# Vision.net
KiCad netlist of a schematic drawn in EAGLE
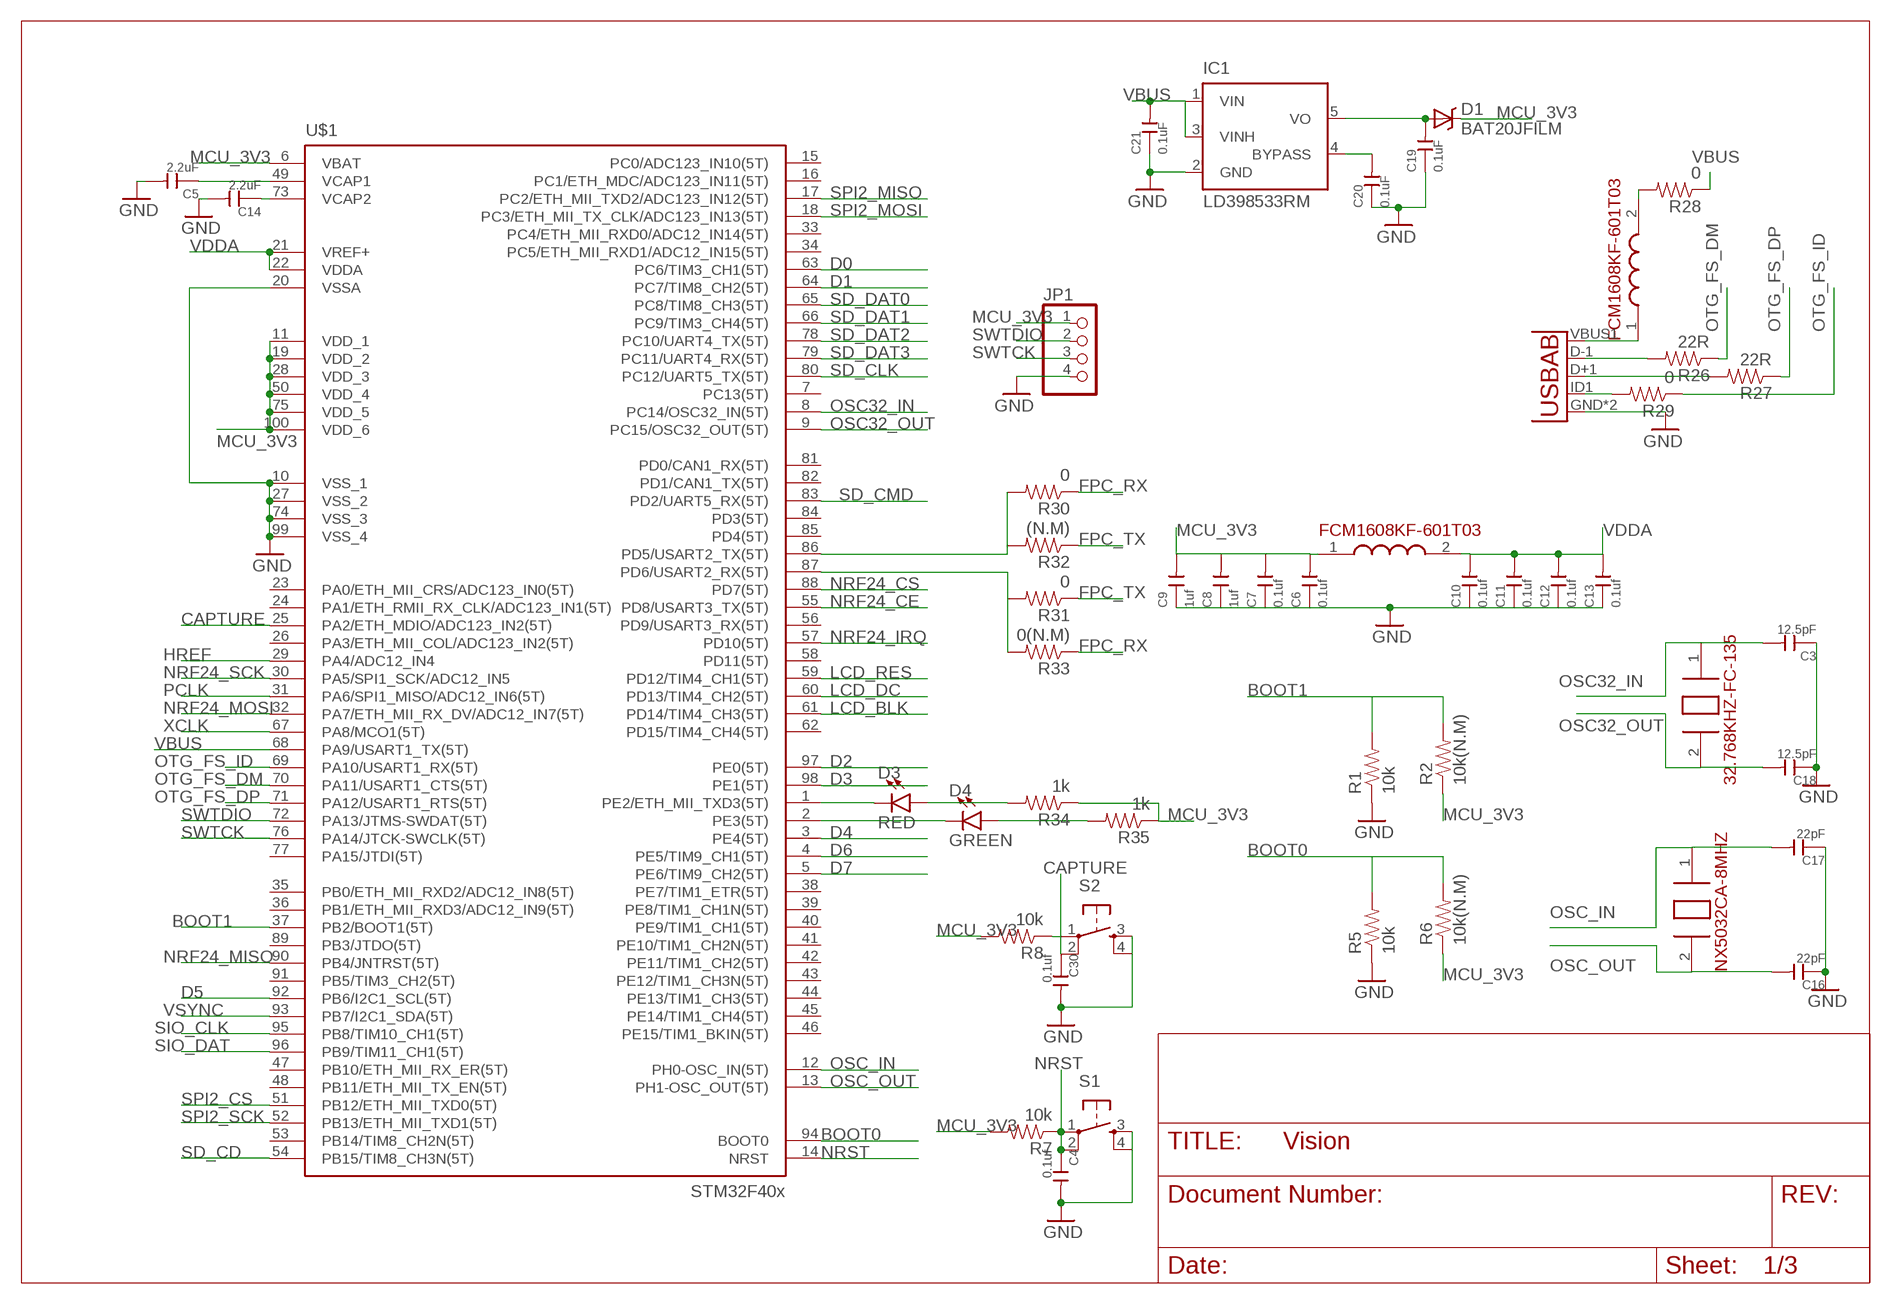
[diagram p0: schematic, sheet 1]
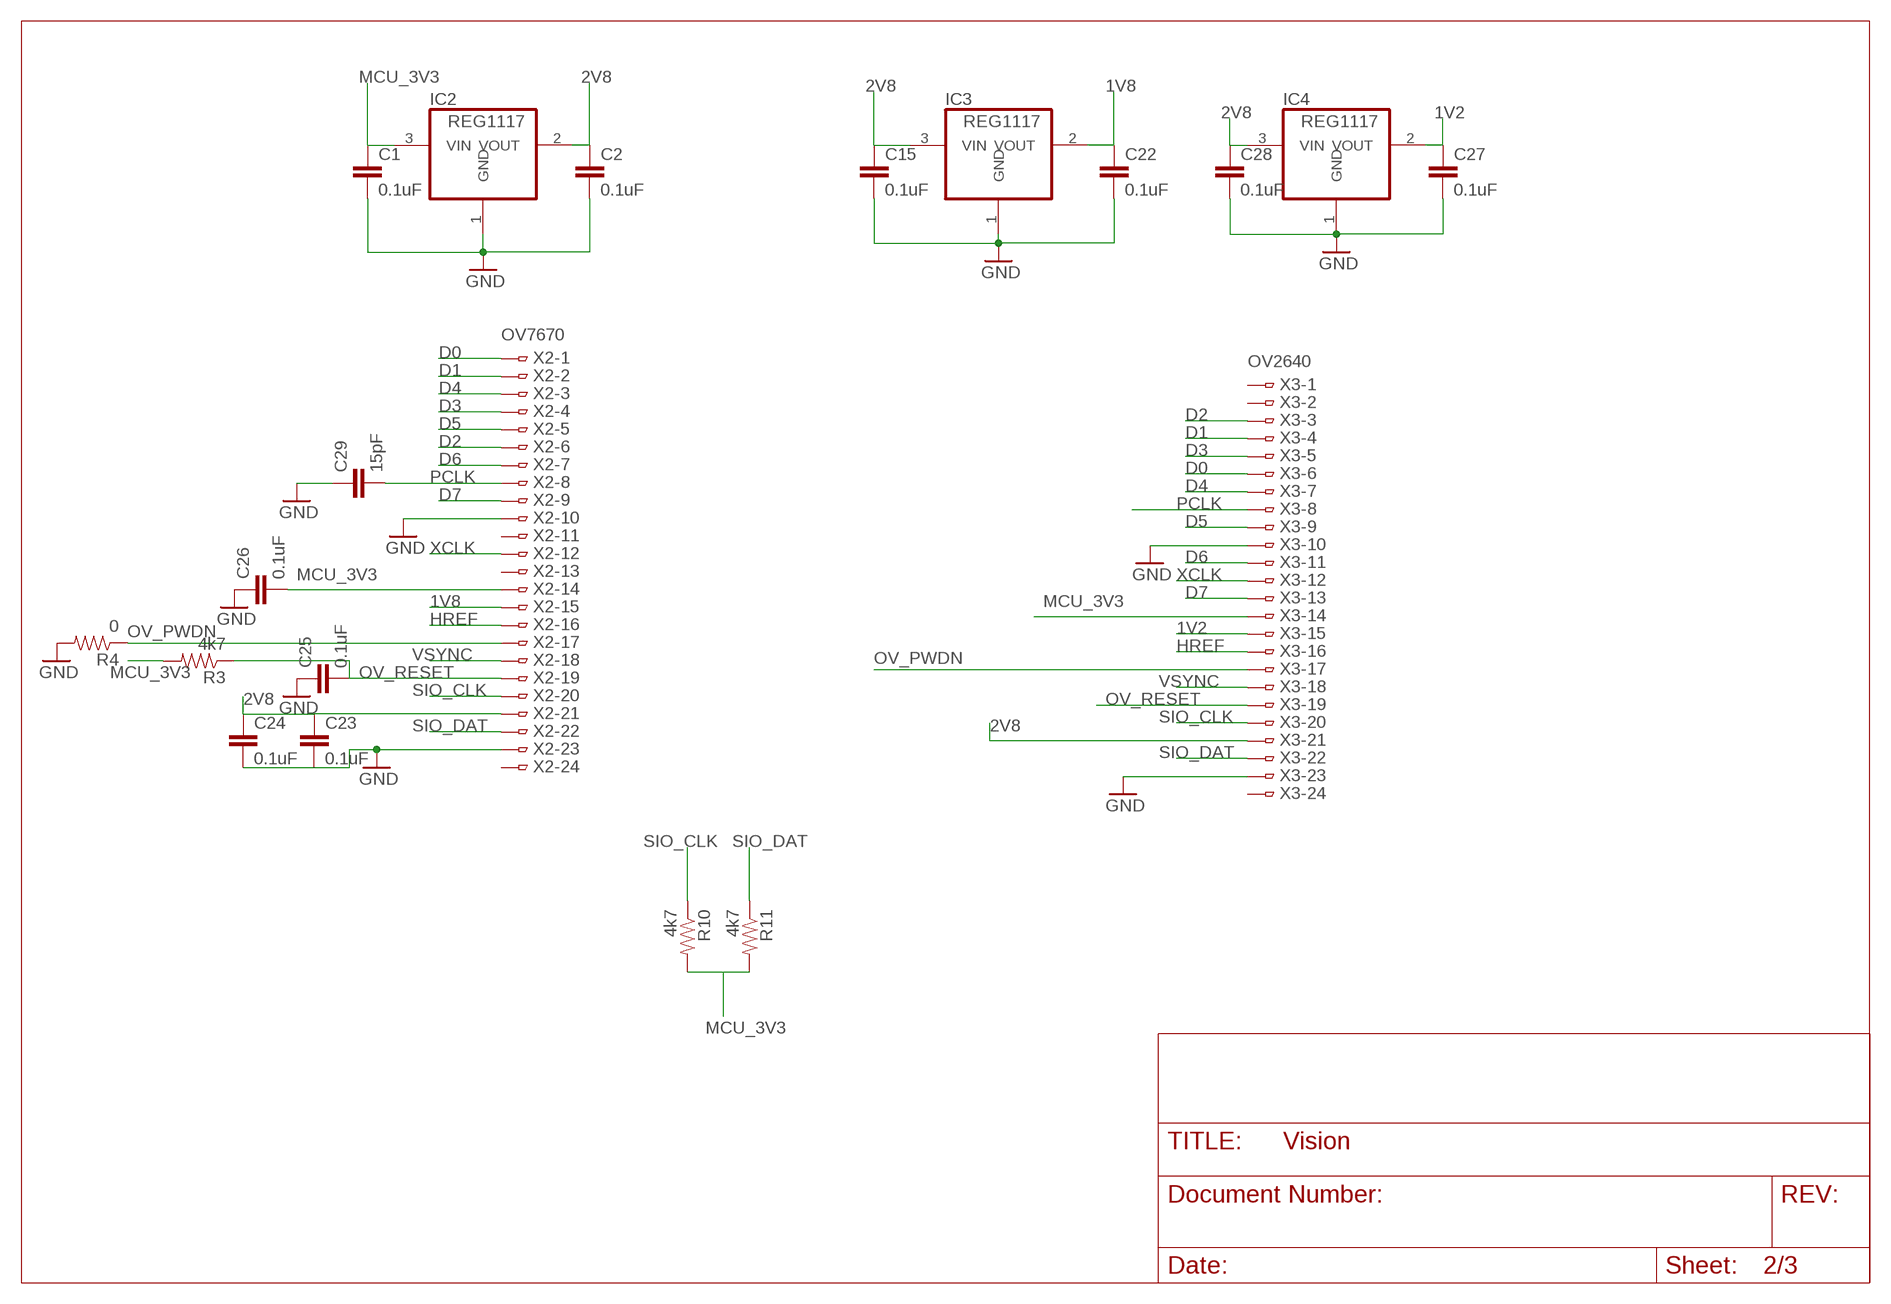
[diagram p1: schematic, sheet 2]
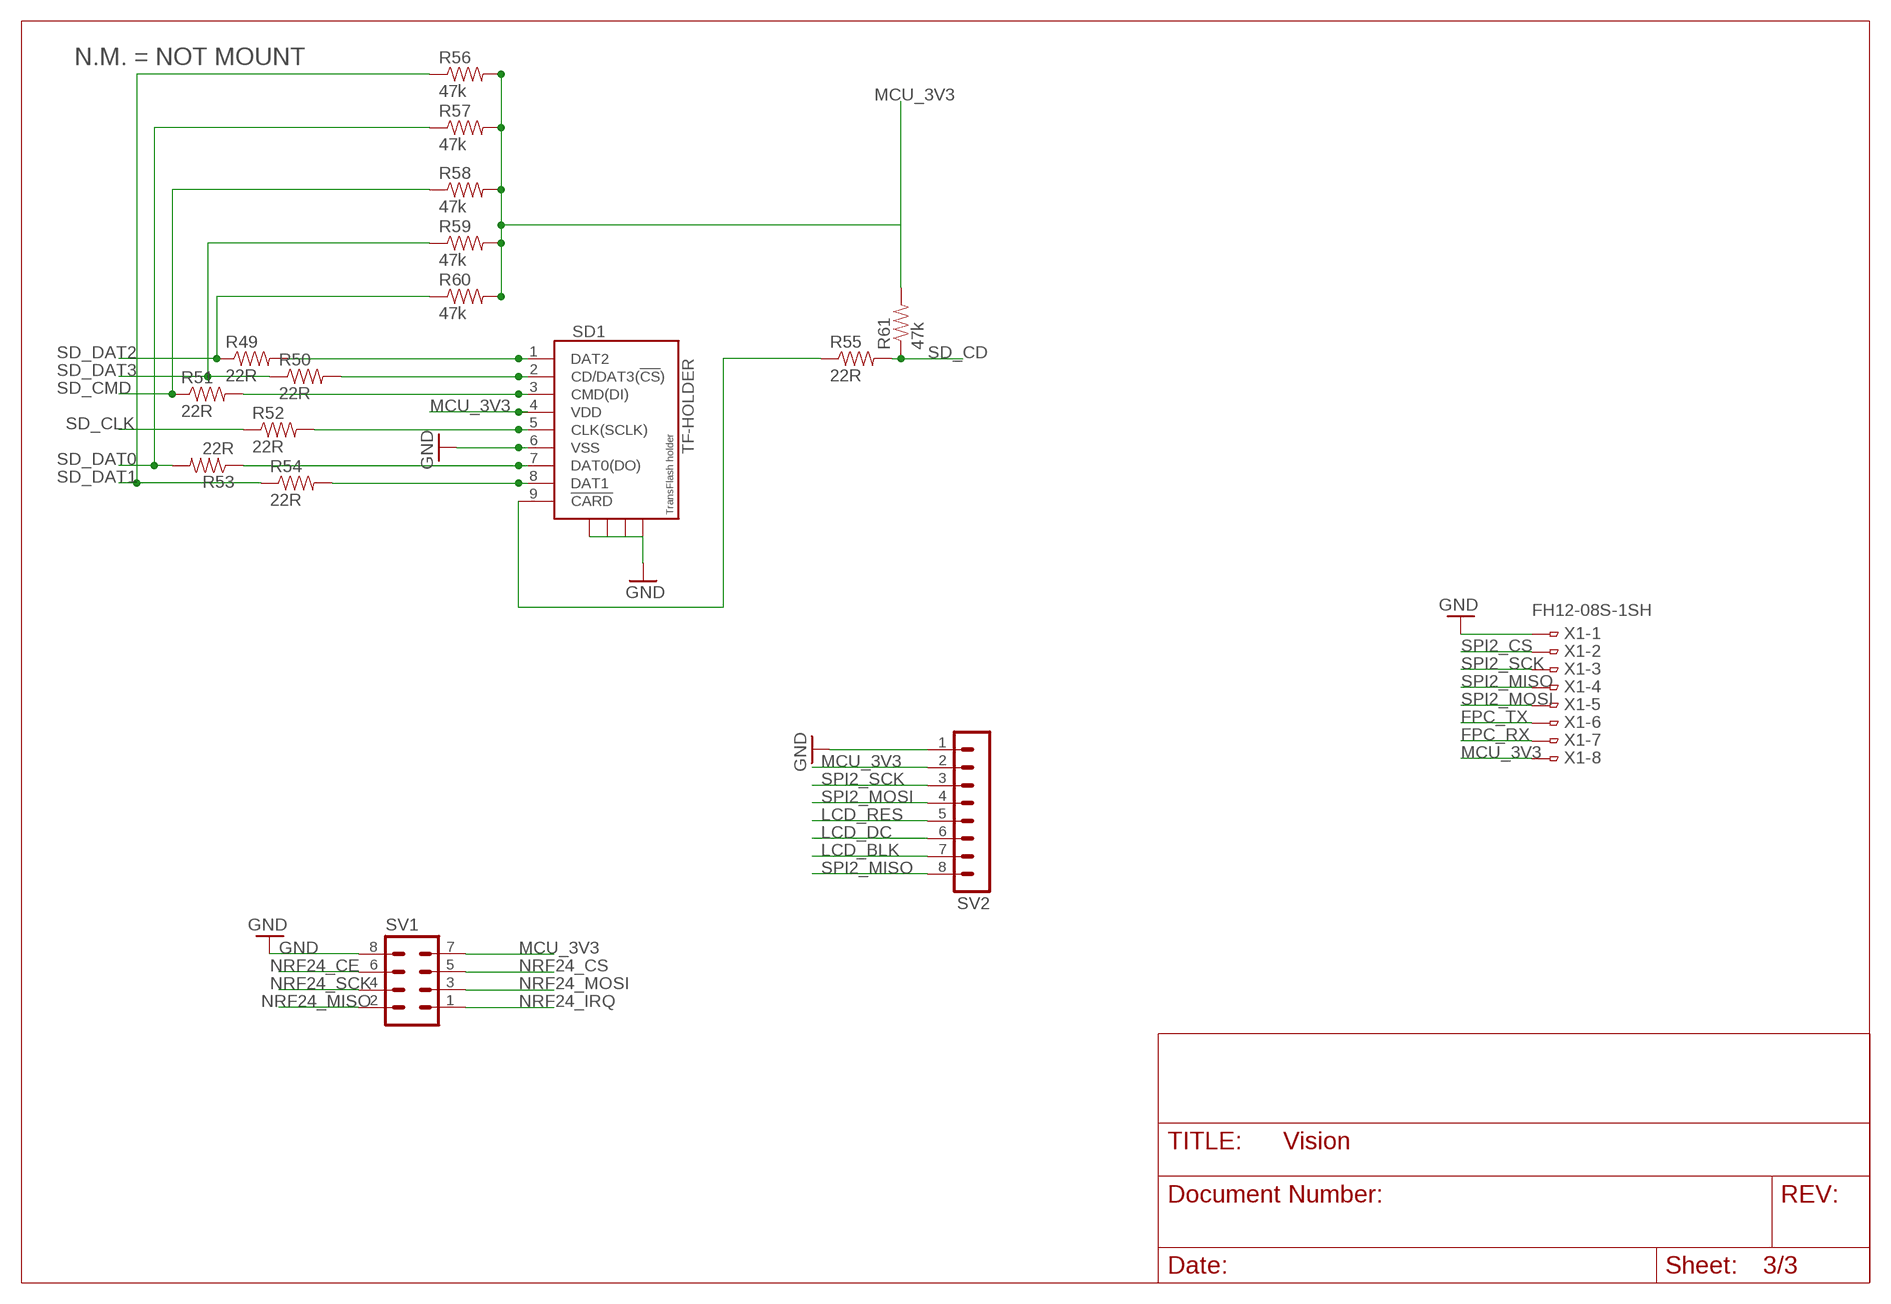
[diagram p2: schematic, sheet 3]

(export (version "E")
  (design (tool "Eeschema 10.0.6"))
  (components
    (comp (ref "C1")
      (value "0.1uF")
      (footprint "eagle-import:0805")
      (libsource (lib "eagle-import") (part "1.0UF-25V-+80/-20(0805)"))
    )
    (comp (ref "C2")
      (value "0.1uF")
      (footprint "eagle-import:0805")
      (libsource (lib "eagle-import") (part "1.0UF-25V-+80/-20(0805)"))
    )
    (comp (ref "C15")
      (value "0.1uF")
      (footprint "eagle-import:0805")
      (libsource (lib "eagle-import") (part "1.0UF-25V-+80/-20(0805)"))
    )
    (comp (ref "C22")
      (value "0.1uF")
      (footprint "eagle-import:0805")
      (libsource (lib "eagle-import") (part "1.0UF-25V-+80/-20(0805)"))
    )
    (comp (ref "C23")
      (value "0.1uF")
      (footprint "eagle-import:0805")
      (libsource (lib "eagle-import") (part "1.0UF-25V-+80/-20(0805)"))
    )
    (comp (ref "C24")
      (value "0.1uF")
      (footprint "eagle-import:0805")
      (libsource (lib "eagle-import") (part "1.0UF-25V-+80/-20(0805)"))
    )
    (comp (ref "C25")
      (value "0.1uF")
      (footprint "eagle-import:0805")
      (libsource (lib "eagle-import") (part "1.0UF-25V-+80/-20(0805)"))
    )
    (comp (ref "C26")
      (value "0.1uF")
      (footprint "eagle-import:0805")
      (libsource (lib "eagle-import") (part "1.0UF-25V-+80/-20(0805)"))
    )
    (comp (ref "C27")
      (value "0.1uF")
      (footprint "eagle-import:0805")
      (libsource (lib "eagle-import") (part "1.0UF-25V-+80/-20(0805)"))
    )
    (comp (ref "C28")
      (value "0.1uF")
      (footprint "eagle-import:0805")
      (libsource (lib "eagle-import") (part "1.0UF-25V-+80/-20(0805)"))
    )
    (comp (ref "C29")
      (value "15pF")
      (footprint "eagle-import:0805")
      (libsource (lib "eagle-import") (part "1.0UF-25V-+80/-20(0805)"))
    )
    (comp (ref "IC2")
      (value "REG1117")
      (footprint "eagle-import:SOT223")
      (libsource (lib "eagle-import") (part "REG1117"))
    )
    (comp (ref "IC3")
      (value "REG1117")
      (footprint "eagle-import:SOT223")
      (libsource (lib "eagle-import") (part "REG1117"))
    )
    (comp (ref "IC4")
      (value "REG1117")
      (footprint "eagle-import:SOT223")
      (libsource (lib "eagle-import") (part "REG1117"))
    )
    (comp (ref "R3")
      (value "4k7")
      (footprint "eagle-import:0603")
      (libsource (lib "eagle-import") (part "0OHM1/10W5%(0603)"))
    )
    (comp (ref "R4")
      (value "0")
      (footprint "eagle-import:0603")
      (libsource (lib "eagle-import") (part "0OHM1/10W5%(0603)"))
    )
    (comp (ref "R10")
      (value "4k7")
      (footprint "eagle-import:0603")
      (libsource (lib "eagle-import") (part "0OHM1/10W5%(0603)"))
    )
    (comp (ref "R11")
      (value "4k7")
      (footprint "eagle-import:0603")
      (libsource (lib "eagle-import") (part "0OHM1/10W5%(0603)"))
    )
    (comp (ref "X2")
      (value "OV7670")
      (footprint "eagle-import:FH12-24S-0.5SH")
      (fields (field (name "MPN") "FH12-24S-0.5SH(55)"))
      (libsource (lib "eagle-import") (part "FH12-24S-0.5SH"))
    )
    (comp (ref "X3")
      (value "OV2640")
      (footprint "eagle-import:FH12-24S-0.5SH")
      (fields (field (name "MPN") "FH12-24S-0.5SH(55)"))
      (libsource (lib "eagle-import") (part "FH12-24S-0.5SH"))
    )
    (comp (ref "R49")
      (value "22R")
      (footprint "eagle-import:0603-RES")
      (libsource (lib "eagle-import") (part "100OHM1/10W1%(0603)"))
    )
    (comp (ref "R50")
      (value "22R")
      (footprint "eagle-import:0603-RES")
      (libsource (lib "eagle-import") (part "100OHM1/10W1%(0603)"))
    )
    (comp (ref "R51")
      (value "22R")
      (footprint "eagle-import:0603-RES")
      (libsource (lib "eagle-import") (part "100OHM1/10W1%(0603)"))
    )
    (comp (ref "R52")
      (value "22R")
      (footprint "eagle-import:0603-RES")
      (libsource (lib "eagle-import") (part "100OHM1/10W1%(0603)"))
    )
    (comp (ref "R53")
      (value "22R")
      (footprint "eagle-import:0603-RES")
      (libsource (lib "eagle-import") (part "100OHM1/10W1%(0603)"))
    )
    (comp (ref "R54")
      (value "22R")
      (footprint "eagle-import:0603-RES")
      (libsource (lib "eagle-import") (part "100OHM1/10W1%(0603)"))
    )
    (comp (ref "R55")
      (value "22R")
      (footprint "eagle-import:0603-RES")
      (libsource (lib "eagle-import") (part "100OHM1/10W1%(0603)"))
    )
    (comp (ref "R56")
      (value "47k")
      (footprint "eagle-import:0603-RES")
      (libsource (lib "eagle-import") (part "100OHM1/10W1%(0603)"))
    )
    (comp (ref "R57")
      (value "47k")
      (footprint "eagle-import:0603-RES")
      (libsource (lib "eagle-import") (part "100OHM1/10W1%(0603)"))
    )
    (comp (ref "R58")
      (value "47k")
      (footprint "eagle-import:0603-RES")
      (libsource (lib "eagle-import") (part "100OHM1/10W1%(0603)"))
    )
    (comp (ref "R59")
      (value "47k")
      (footprint "eagle-import:0603-RES")
      (libsource (lib "eagle-import") (part "100OHM1/10W1%(0603)"))
    )
    (comp (ref "R60")
      (value "47k")
      (footprint "eagle-import:0603-RES")
      (libsource (lib "eagle-import") (part "100OHM1/10W1%(0603)"))
    )
    (comp (ref "R61")
      (value "47k")
      (footprint "eagle-import:0603-RES")
      (libsource (lib "eagle-import") (part "100OHM1/10W1%(0603)"))
    )
    (comp (ref "SD1")
      (value "TF-HOLDER")
      (footprint "eagle-import:TF-PULL")
      (libsource (lib "eagle-import") (part "TF-HOLDER"))
    )
    (comp (ref "SV1")
      (value "MA04-2")
      (footprint "eagle-import:MA04-2")
      (libsource (lib "eagle-import") (part "MA04-2"))
    )
    (comp (ref "SV2")
      (value "MA08-1")
      (footprint "eagle-import:MA08-1")
      (libsource (lib "eagle-import") (part "MA08-1"))
    )
    (comp (ref "X1")
      (value "FH12-08S-1SH")
      (footprint "eagle-import:FH12-08S-1SH")
      (libsource (lib "eagle-import") (part "FH12-08S-1SH"))
    )
    (comp (ref "C3")
      (value "12.5pF")
      (footprint "eagle-import:C0603")
      (fields (field (name "MPN") "CC0603KRX5R6BB475"))
      (libsource (lib "eagle-import") (part "CERAMIC-4.7UF-10V-10%-X5R(0603)"))
    )
    (comp (ref "C4")
      (value "0.1uf")
      (footprint "eagle-import:C0603")
      (fields (field (name "MPN") "CC0603KRX5R6BB475"))
      (libsource (lib "eagle-import") (part "CERAMIC-4.7UF-10V-10%-X5R(0603)"))
    )
    (comp (ref "C5")
      (value "2.2uF")
      (footprint "eagle-import:C0603")
      (libsource (lib "eagle-import") (part "CERAMIC-0.5PF-50V-0.1PF-NPO(0603)"))
    )
    (comp (ref "C6")
      (value "0.1uf")
      (footprint "eagle-import:C0603")
      (fields (field (name "MPN") "CC0603KRX5R6BB475"))
      (libsource (lib "eagle-import") (part "CERAMIC-4.7UF-10V-10%-X5R(0603)"))
    )
    (comp (ref "C7")
      (value "0.1uf")
      (footprint "eagle-import:C0603")
      (fields (field (name "MPN") "CC0603KRX5R6BB475"))
      (libsource (lib "eagle-import") (part "CERAMIC-4.7UF-10V-10%-X5R(0603)"))
    )
    (comp (ref "C8")
      (value "1uf")
      (footprint "eagle-import:C0603")
      (fields (field (name "MPN") "CC0603KRX5R6BB475"))
      (libsource (lib "eagle-import") (part "CERAMIC-4.7UF-10V-10%-X5R(0603)"))
    )
    (comp (ref "C9")
      (value "1uf")
      (footprint "eagle-import:C0603")
      (fields (field (name "MPN") "CC0603KRX5R6BB475"))
      (libsource (lib "eagle-import") (part "CERAMIC-4.7UF-10V-10%-X5R(0603)"))
    )
    (comp (ref "C10")
      (value "0.1uf")
      (footprint "eagle-import:C0603")
      (fields (field (name "MPN") "CC0603KRX5R6BB475"))
      (libsource (lib "eagle-import") (part "CERAMIC-4.7UF-10V-10%-X5R(0603)"))
    )
    (comp (ref "C11")
      (value "0.1uf")
      (footprint "eagle-import:C0603")
      (fields (field (name "MPN") "CC0603KRX5R6BB475"))
      (libsource (lib "eagle-import") (part "CERAMIC-4.7UF-10V-10%-X5R(0603)"))
    )
    (comp (ref "C12")
      (value "0.1uf")
      (footprint "eagle-import:C0603")
      (fields (field (name "MPN") "CC0603KRX5R6BB475"))
      (libsource (lib "eagle-import") (part "CERAMIC-4.7UF-10V-10%-X5R(0603)"))
    )
    (comp (ref "C13")
      (value "0.1uf")
      (footprint "eagle-import:C0603")
      (fields (field (name "MPN") "CC0603KRX5R6BB475"))
      (libsource (lib "eagle-import") (part "CERAMIC-4.7UF-10V-10%-X5R(0603)"))
    )
    (comp (ref "C14")
      (value "2.2uF")
      (footprint "eagle-import:C0603")
      (libsource (lib "eagle-import") (part "CERAMIC-0.5PF-50V-0.1PF-NPO(0603)"))
    )
    (comp (ref "C16")
      (value "22pF")
      (footprint "eagle-import:C0603")
      (fields (field (name "MPN") "CC0603KRX5R6BB475"))
      (libsource (lib "eagle-import") (part "CERAMIC-4.7UF-10V-10%-X5R(0603)"))
    )
    (comp (ref "C17")
      (value "22pF")
      (footprint "eagle-import:C0603")
      (fields (field (name "MPN") "CC0603KRX5R6BB475"))
      (libsource (lib "eagle-import") (part "CERAMIC-4.7UF-10V-10%-X5R(0603)"))
    )
    (comp (ref "C18")
      (value "12.5pF")
      (footprint "eagle-import:C0603")
      (fields (field (name "MPN") "CC0603KRX5R6BB475"))
      (libsource (lib "eagle-import") (part "CERAMIC-4.7UF-10V-10%-X5R(0603)"))
    )
    (comp (ref "C19")
      (value "0.1uF")
      (footprint "eagle-import:C0603")
      (libsource (lib "eagle-import") (part "CERAMIC-0.5PF-50V-0.1PF-NPO(0603)"))
    )
    (comp (ref "C20")
      (value "0.1uF")
      (footprint "eagle-import:C0603")
      (libsource (lib "eagle-import") (part "CERAMIC-0.5PF-50V-0.1PF-NPO(0603)"))
    )
    (comp (ref "C21")
      (value "0.1uF")
      (footprint "eagle-import:C0603")
      (libsource (lib "eagle-import") (part "CERAMIC-0.5PF-50V-0.1PF-NPO(0603)"))
    )
    (comp (ref "C30")
      (value "0.1uf")
      (footprint "eagle-import:C0603")
      (fields (field (name "MPN") "CC0603KRX5R6BB475"))
      (libsource (lib "eagle-import") (part "CERAMIC-4.7UF-10V-10%-X5R(0603)"))
    )
    (comp (ref "D1")
      (value "BAT20JFILM")
      (footprint "eagle-import:SOD-323")
      (libsource (lib "eagle-import") (part "BAT20JFILM"))
    )
    (comp (ref "D3")
      (value "RED")
      (footprint "eagle-import:LED-0603")
      (libsource (lib "eagle-import") (part "LED-BLUE0603"))
    )
    (comp (ref "D4")
      (value "GREEN")
      (footprint "eagle-import:LED-0603")
      (libsource (lib "eagle-import") (part "LED-BLUE0603"))
    )
    (comp (ref "IC1")
      (value "LD398533RM")
      (footprint "eagle-import:SOT23-5L")
      (libsource (lib "eagle-import") (part "LD3985M33R"))
    )
    (comp (ref "JP1")
      (value "PINHD-1X4")
      (footprint "eagle-import:1X04")
      (libsource (lib "eagle-import") (part "PINHD-1X4"))
    )
    (comp (ref "R1")
      (value "10k")
      (footprint "eagle-import:0603")
      (libsource (lib "eagle-import") (part "0OHM1/10W5%(0603)"))
    )
    (comp (ref "R2")
      (value "10k(N.M)")
      (footprint "eagle-import:0603")
      (libsource (lib "eagle-import") (part "0OHM1/10W5%(0603)"))
    )
    (comp (ref "R5")
      (value "10k")
      (footprint "eagle-import:0603")
      (libsource (lib "eagle-import") (part "0OHM1/10W5%(0603)"))
    )
    (comp (ref "R6")
      (value "10k(N.M)")
      (footprint "eagle-import:0603")
      (libsource (lib "eagle-import") (part "0OHM1/10W5%(0603)"))
    )
    (comp (ref "R7")
      (value "10k")
      (footprint "eagle-import:0603")
      (libsource (lib "eagle-import") (part "0OHM1/10W5%(0603)"))
    )
    (comp (ref "R8")
      (value "10k")
      (footprint "eagle-import:0603")
      (libsource (lib "eagle-import") (part "0OHM1/10W5%(0603)"))
    )
    (comp (ref "R26")
      (value "22R")
      (footprint "eagle-import:0603-RES")
      (libsource (lib "eagle-import") (part "390OHM1/10W1%(0603)"))
    )
    (comp (ref "R27")
      (value "22R")
      (footprint "eagle-import:0603-RES")
      (libsource (lib "eagle-import") (part "390OHM1/10W1%(0603)"))
    )
    (comp (ref "R28")
      (value "0")
      (footprint "eagle-import:0603-RES")
      (libsource (lib "eagle-import") (part "390OHM1/10W1%(0603)"))
    )
    (comp (ref "R29")
      (value "0")
      (footprint "eagle-import:0603-RES")
      (libsource (lib "eagle-import") (part "390OHM1/10W1%(0603)"))
    )
    (comp (ref "R30")
      (value "0")
      (footprint "eagle-import:0603")
      (libsource (lib "eagle-import") (part "0OHM1/10W5%(0603)"))
    )
    (comp (ref "R31")
      (value "0")
      (footprint "eagle-import:0603")
      (libsource (lib "eagle-import") (part "0OHM1/10W5%(0603)"))
    )
    (comp (ref "R32")
      (value "(N.M)")
      (footprint "eagle-import:0603")
      (libsource (lib "eagle-import") (part "0OHM1/10W5%(0603)"))
    )
    (comp (ref "R33")
      (value "0(N.M)")
      (footprint "eagle-import:0603")
      (libsource (lib "eagle-import") (part "0OHM1/10W5%(0603)"))
    )
    (comp (ref "R34")
      (value "1k")
      (footprint "eagle-import:0603")
      (libsource (lib "eagle-import") (part "0OHM1/10W5%(0603)"))
    )
    (comp (ref "R35")
      (value "1k")
      (footprint "eagle-import:0603")
      (libsource (lib "eagle-import") (part "0OHM1/10W5%(0603)"))
    )
    (comp (ref "S1")
      (value "TAC_SWITCHSMD")
      (footprint "eagle-import:TACTILE_SWITCH_SMD")
      (libsource (lib "eagle-import") (part "TAC_SWITCHSMD"))
    )
    (comp (ref "S2")
      (value "TAC_SWITCHSMD")
      (footprint "eagle-import:TACTILE_SWITCH_SMD")
      (libsource (lib "eagle-import") (part "TAC_SWITCHSMD"))
    )
    (comp (ref "U$1")
      (value "STM32F407V")
      (footprint "eagle-import:TQFP100")
      (libsource (lib "eagle-import") (part "STM32F407V"))
    )
    (comp (ref "U$2")
      (value "NX5032CA-8MHZ")
      (footprint "eagle-import:NX5032CA-8MHZ")
      (libsource (lib "eagle-import") (part "NX5032CA-8MHZ"))
    )
    (comp (ref "U$3")
      (value "FCM1608KF-601T03")
      (footprint "eagle-import:FCM1608KF-601T03")
      (libsource (lib "eagle-import") (part "FCM1608KF-601T03"))
    )
    (comp (ref "U$4")
      (value "32.768KHZ-FC-135")
      (footprint "eagle-import:32.768KHZ-FC-135")
      (libsource (lib "eagle-import") (part "32.768KHZ-FC-135"))
    )
    (comp (ref "U$5")
      (value "FCM1608KF-601T03")
      (footprint "eagle-import:FCM1608KF-601T03")
      (libsource (lib "eagle-import") (part "FCM1608KF-601T03"))
    )
    (comp (ref "U4")
      (value "USB\"\"")
      (footprint "eagle-import:USB-MICRO-SMD")
      (libsource (lib "eagle-import") (part "USB{dblquote}{dblquote}"))
    )
  )
  (nets
    (net (code "1") (name "1V2") (class "Default")
      (node (ref "C27") (pin "1") (pinfunction "1_1") (pintype "passive"))
      (node (ref "IC4") (pin "2") (pinfunction "VOUT_2") (pintype "output"))
      (node (ref "X3") (pin "15") (pinfunction "1_15") (pintype "passive"))
    )
    (net (code "2") (name "1V8") (class "Default")
      (node (ref "C22") (pin "1") (pinfunction "1_1") (pintype "passive"))
      (node (ref "IC3") (pin "2") (pinfunction "VOUT_2") (pintype "output"))
      (node (ref "X2") (pin "15") (pinfunction "1_15") (pintype "passive"))
    )
    (net (code "3") (name "2V8") (class "Default")
      (node (ref "C15") (pin "1") (pinfunction "1_1") (pintype "passive"))
      (node (ref "C2") (pin "1") (pinfunction "1_1") (pintype "passive"))
      (node (ref "C23") (pin "1") (pinfunction "1_1") (pintype "passive"))
      (node (ref "C24") (pin "1") (pinfunction "1_1") (pintype "passive"))
      (node (ref "C28") (pin "1") (pinfunction "1_1") (pintype "passive"))
      (node (ref "IC2") (pin "2") (pinfunction "VOUT_2") (pintype "output"))
      (node (ref "IC3") (pin "3") (pinfunction "VIN_3") (pintype "input"))
      (node (ref "IC4") (pin "3") (pinfunction "VIN_3") (pintype "input"))
      (node (ref "X2") (pin "21") (pinfunction "1_21") (pintype "passive"))
      (node (ref "X3") (pin "21") (pinfunction "1_21") (pintype "passive"))
    )
    (net (code "4") (name "BOOT0") (class "Default")
      (node (ref "R5") (pin "2") (pinfunction "2_2") (pintype "passive"))
      (node (ref "R6") (pin "2") (pinfunction "2_2") (pintype "passive"))
      (node (ref "U$1") (pin "94") (pinfunction "BOOT0_94") (pintype "bidirectional"))
    )
    (net (code "5") (name "BOOT1") (class "Default")
      (node (ref "R1") (pin "2") (pinfunction "2_2") (pintype "passive"))
      (node (ref "R2") (pin "2") (pinfunction "2_2") (pintype "passive"))
      (node (ref "U$1") (pin "37") (pinfunction "PB2/BOOT1(5T)_37") (pintype "bidirectional"))
    )
    (net (code "6") (name "CAPTURE") (class "Default")
      (node (ref "C30") (pin "1") (pinfunction "1_1") (pintype "passive"))
      (node (ref "R8") (pin "1") (pinfunction "1_1") (pintype "passive"))
      (node (ref "S2") (pin "1") (pinfunction "1_1") (pintype "passive"))
      (node (ref "S2") (pin "2") (pinfunction "2_2") (pintype "passive"))
      (node (ref "U$1") (pin "25") (pinfunction "PA2/ETH_MDIO/ADC123_IN2(5T)_25") (pintype "bidirectional"))
    )
    (net (code "7") (name "D0") (class "Default")
      (node (ref "U$1") (pin "63") (pinfunction "PC6/TIM3_CH1(5T)_63") (pintype "bidirectional"))
      (node (ref "X2") (pin "1") (pinfunction "1_1") (pintype "passive"))
      (node (ref "X3") (pin "6") (pinfunction "1_6") (pintype "passive"))
    )
    (net (code "8") (name "D1") (class "Default")
      (node (ref "U$1") (pin "64") (pinfunction "PC7/TIM8_CH2(5T)_64") (pintype "bidirectional"))
      (node (ref "X2") (pin "2") (pinfunction "1_2") (pintype "passive"))
      (node (ref "X3") (pin "4") (pinfunction "1_4") (pintype "passive"))
    )
    (net (code "9") (name "D2") (class "Default")
      (node (ref "U$1") (pin "97") (pinfunction "PE0(5T)_97") (pintype "bidirectional"))
      (node (ref "X2") (pin "6") (pinfunction "1_6") (pintype "passive"))
      (node (ref "X3") (pin "3") (pinfunction "1_3") (pintype "passive"))
    )
    (net (code "10") (name "D3") (class "Default")
      (node (ref "U$1") (pin "98") (pinfunction "PE1(5T)_98") (pintype "bidirectional"))
      (node (ref "X2") (pin "4") (pinfunction "1_4") (pintype "passive"))
      (node (ref "X3") (pin "5") (pinfunction "1_5") (pintype "passive"))
    )
    (net (code "11") (name "D4") (class "Default")
      (node (ref "U$1") (pin "3") (pinfunction "PE4(5T)_3") (pintype "bidirectional"))
      (node (ref "X2") (pin "3") (pinfunction "1_3") (pintype "passive"))
      (node (ref "X3") (pin "7") (pinfunction "1_7") (pintype "passive"))
    )
    (net (code "12") (name "D5") (class "Default")
      (node (ref "U$1") (pin "92") (pinfunction "PB6/I2C1_SCL(5T)_92") (pintype "bidirectional"))
      (node (ref "X2") (pin "5") (pinfunction "1_5") (pintype "passive"))
      (node (ref "X3") (pin "9") (pinfunction "1_9") (pintype "passive"))
    )
    (net (code "13") (name "D6") (class "Default")
      (node (ref "U$1") (pin "4") (pinfunction "PE5/TIM9_CH1(5T)_4") (pintype "bidirectional"))
      (node (ref "X2") (pin "7") (pinfunction "1_7") (pintype "passive"))
      (node (ref "X3") (pin "11") (pinfunction "1_11") (pintype "passive"))
    )
    (net (code "14") (name "D7") (class "Default")
      (node (ref "U$1") (pin "5") (pinfunction "PE6/TIM9_CH2(5T)_5") (pintype "bidirectional"))
      (node (ref "X2") (pin "9") (pinfunction "1_9") (pintype "passive"))
      (node (ref "X3") (pin "13") (pinfunction "1_13") (pintype "passive"))
    )
    (net (code "15") (name "FPC_RX") (class "Default")
      (node (ref "R30") (pin "1") (pinfunction "1_1") (pintype "passive"))
      (node (ref "R33") (pin "1") (pinfunction "1_1") (pintype "passive"))
      (node (ref "X1") (pin "7") (pinfunction "1_7") (pintype "passive"))
    )
    (net (code "16") (name "FPC_TX") (class "Default")
      (node (ref "R31") (pin "1") (pinfunction "1_1") (pintype "passive"))
      (node (ref "R32") (pin "1") (pinfunction "1_1") (pintype "passive"))
      (node (ref "X1") (pin "6") (pinfunction "1_6") (pintype "passive"))
    )
    (net (code "17") (name "GND") (class "Default")
      (node (ref "C1") (pin "2") (pinfunction "2_2") (pintype "passive"))
      (node (ref "C10") (pin "1") (pinfunction "1_1") (pintype "passive"))
      (node (ref "C11") (pin "1") (pinfunction "1_1") (pintype "passive"))
      (node (ref "C12") (pin "1") (pinfunction "1_1") (pintype "passive"))
      (node (ref "C13") (pin "1") (pinfunction "1_1") (pintype "passive"))
      (node (ref "C14") (pin "2") (pinfunction "2_2") (pintype "passive"))
      (node (ref "C15") (pin "2") (pinfunction "2_2") (pintype "passive"))
      (node (ref "C16") (pin "1") (pinfunction "1_1") (pintype "passive"))
      (node (ref "C17") (pin "1") (pinfunction "1_1") (pintype "passive"))
      (node (ref "C18") (pin "1") (pinfunction "1_1") (pintype "passive"))
      (node (ref "C19") (pin "1") (pinfunction "1_1") (pintype "passive"))
      (node (ref "C2") (pin "2") (pinfunction "2_2") (pintype "passive"))
      (node (ref "C20") (pin "1") (pinfunction "1_1") (pintype "passive"))
      (node (ref "C21") (pin "1") (pinfunction "1_1") (pintype "passive"))
      (node (ref "C22") (pin "2") (pinfunction "2_2") (pintype "passive"))
      (node (ref "C23") (pin "2") (pinfunction "2_2") (pintype "passive"))
      (node (ref "C24") (pin "2") (pinfunction "2_2") (pintype "passive"))
      (node (ref "C25") (pin "1") (pinfunction "1_1") (pintype "passive"))
      (node (ref "C26") (pin "1") (pinfunction "1_1") (pintype "passive"))
      (node (ref "C27") (pin "2") (pinfunction "2_2") (pintype "passive"))
      (node (ref "C28") (pin "2") (pinfunction "2_2") (pintype "passive"))
      (node (ref "C29") (pin "1") (pinfunction "1_1") (pintype "passive"))
      (node (ref "C3") (pin "1") (pinfunction "1_1") (pintype "passive"))
      (node (ref "C30") (pin "2") (pinfunction "2_2") (pintype "passive"))
      (node (ref "C4") (pin "2") (pinfunction "2_2") (pintype "passive"))
      (node (ref "C5") (pin "2") (pinfunction "2_2") (pintype "passive"))
      (node (ref "C6") (pin "1") (pinfunction "1_1") (pintype "passive"))
      (node (ref "C7") (pin "1") (pinfunction "1_1") (pintype "passive"))
      (node (ref "C8") (pin "1") (pinfunction "1_1") (pintype "passive"))
      (node (ref "C9") (pin "1") (pinfunction "1_1") (pintype "passive"))
      (node (ref "IC1") (pin "2") (pinfunction "GND_2") (pintype "power_in"))
      (node (ref "IC2") (pin "1") (pinfunction "GND_1") (pintype "power_in"))
      (node (ref "IC3") (pin "1") (pinfunction "GND_1") (pintype "power_in"))
      (node (ref "IC4") (pin "1") (pinfunction "GND_1") (pintype "power_in"))
      (node (ref "JP1") (pin "4") (pinfunction "4_4") (pintype "passive"))
      (node (ref "R1") (pin "1") (pinfunction "1_1") (pintype "passive"))
      (node (ref "R4") (pin "2") (pinfunction "2_2") (pintype "passive"))
      (node (ref "R5") (pin "1") (pinfunction "1_1") (pintype "passive"))
      (node (ref "S1") (pin "3") (pinfunction "3_3") (pintype "passive"))
      (node (ref "S1") (pin "4") (pinfunction "4_4") (pintype "passive"))
      (node (ref "S2") (pin "3") (pinfunction "3_3") (pintype "passive"))
      (node (ref "S2") (pin "4") (pinfunction "4_4") (pintype "passive"))
      (node (ref "SD1") (pin "6") (pinfunction "VSS_6") (pintype "power_in"))
      (node (ref "SD1") (pin "S1") (pinfunction "S1_S1") (pintype "passive"))
      (node (ref "SD1") (pin "S2") (pinfunction "S2_S2") (pintype "passive"))
      (node (ref "SD1") (pin "S3") (pinfunction "S3_S3") (pintype "passive"))
      (node (ref "SD1") (pin "S4") (pinfunction "S4_S4") (pintype "passive"))
      (node (ref "SV1") (pin "8") (pinfunction "8_8") (pintype "passive"))
      (node (ref "SV2") (pin "1") (pinfunction "1_1") (pintype "passive"))
      (node (ref "U$1") (pin "10") (pinfunction "VSS_1_10") (pintype "bidirectional"))
      (node (ref "U$1") (pin "20") (pinfunction "VSSA_20") (pintype "bidirectional"))
      (node (ref "U$1") (pin "27") (pinfunction "VSS_2_27") (pintype "bidirectional"))
      (node (ref "U$1") (pin "74") (pinfunction "VSS_3_74") (pintype "bidirectional"))
      (node (ref "U$1") (pin "99") (pinfunction "VSS_4_99") (pintype "bidirectional"))
      (node (ref "U4") (pin "GND") (pinfunction "GND_GND") (pintype "bidirectional"))
      (node (ref "U4") (pin "GND1") (pinfunction "GND_GND1") (pintype "bidirectional"))
      (node (ref "X1") (pin "1") (pinfunction "1_1") (pintype "passive"))
      (node (ref "X2") (pin "10") (pinfunction "1_10") (pintype "passive"))
      (node (ref "X2") (pin "23") (pinfunction "1_23") (pintype "passive"))
      (node (ref "X3") (pin "10") (pinfunction "1_10") (pintype "passive"))
      (node (ref "X3") (pin "23") (pinfunction "1_23") (pintype "passive"))
    )
    (net (code "18") (name "HREF") (class "Default")
      (node (ref "U$1") (pin "29") (pinfunction "PA4/ADC12_IN4_29") (pintype "bidirectional"))
      (node (ref "X2") (pin "16") (pinfunction "1_16") (pintype "passive"))
      (node (ref "X3") (pin "16") (pinfunction "1_16") (pintype "passive"))
    )
    (net (code "19") (name "LCD_BLK") (class "Default")
      (node (ref "SV2") (pin "7") (pinfunction "7_7") (pintype "passive"))
      (node (ref "U$1") (pin "61") (pinfunction "PD14/TIM4_CH3(5T)_61") (pintype "bidirectional"))
    )
    (net (code "20") (name "LCD_DC") (class "Default")
      (node (ref "SV2") (pin "6") (pinfunction "6_6") (pintype "passive"))
      (node (ref "U$1") (pin "60") (pinfunction "PD13/TIM4_CH2(5T)_60") (pintype "bidirectional"))
    )
    (net (code "21") (name "LCD_RES") (class "Default")
      (node (ref "SV2") (pin "5") (pinfunction "5_5") (pintype "passive"))
      (node (ref "U$1") (pin "59") (pinfunction "PD12/TIM4_CH1(5T)_59") (pintype "bidirectional"))
    )
    (net (code "22") (name "MCU_3V3") (class "Default")
      (node (ref "C1") (pin "1") (pinfunction "1_1") (pintype "passive"))
      (node (ref "C26") (pin "2") (pinfunction "2_2") (pintype "passive"))
      (node (ref "C6") (pin "2") (pinfunction "2_2") (pintype "passive"))
      (node (ref "C7") (pin "2") (pinfunction "2_2") (pintype "passive"))
      (node (ref "C8") (pin "2") (pinfunction "2_2") (pintype "passive"))
      (node (ref "C9") (pin "2") (pinfunction "2_2") (pintype "passive"))
      (node (ref "D1") (pin "1") (pinfunction "C_1") (pintype "passive"))
      (node (ref "IC2") (pin "3") (pinfunction "VIN_3") (pintype "input"))
      (node (ref "JP1") (pin "1") (pinfunction "1_1") (pintype "passive"))
      (node (ref "R10") (pin "2") (pinfunction "2_2") (pintype "passive"))
      (node (ref "R11") (pin "2") (pinfunction "2_2") (pintype "passive"))
      (node (ref "R2") (pin "1") (pinfunction "1_1") (pintype "passive"))
      (node (ref "R3") (pin "2") (pinfunction "2_2") (pintype "passive"))
      (node (ref "R34") (pin "1") (pinfunction "1_1") (pintype "passive"))
      (node (ref "R35") (pin "1") (pinfunction "1_1") (pintype "passive"))
      (node (ref "R56") (pin "2") (pinfunction "2_2") (pintype "passive"))
      (node (ref "R57") (pin "2") (pinfunction "2_2") (pintype "passive"))
      (node (ref "R58") (pin "2") (pinfunction "2_2") (pintype "passive"))
      (node (ref "R59") (pin "2") (pinfunction "2_2") (pintype "passive"))
      (node (ref "R6") (pin "1") (pinfunction "1_1") (pintype "passive"))
      (node (ref "R60") (pin "2") (pinfunction "2_2") (pintype "passive"))
      (node (ref "R61") (pin "2") (pinfunction "2_2") (pintype "passive"))
      (node (ref "R7") (pin "2") (pinfunction "2_2") (pintype "passive"))
      (node (ref "R8") (pin "2") (pinfunction "2_2") (pintype "passive"))
      (node (ref "SD1") (pin "4") (pinfunction "VDD_4") (pintype "power_in"))
      (node (ref "SV1") (pin "7") (pinfunction "7_7") (pintype "passive"))
      (node (ref "SV2") (pin "2") (pinfunction "2_2") (pintype "passive"))
      (node (ref "U$1") (pin "100") (pinfunction "VDD_6_100") (pintype "bidirectional"))
      (node (ref "U$1") (pin "11") (pinfunction "VDD_1_11") (pintype "bidirectional"))
      (node (ref "U$1") (pin "19") (pinfunction "VDD_2_19") (pintype "bidirectional"))
      (node (ref "U$1") (pin "28") (pinfunction "VDD_3_28") (pintype "bidirectional"))
      (node (ref "U$1") (pin "50") (pinfunction "VDD_4_50") (pintype "bidirectional"))
      (node (ref "U$1") (pin "6") (pinfunction "VBAT_6") (pintype "bidirectional"))
      (node (ref "U$1") (pin "75") (pinfunction "VDD_5_75") (pintype "bidirectional"))
      (node (ref "U$3") (pin "1") (pinfunction "1.IN_1") (pintype "bidirectional"))
      (node (ref "X1") (pin "8") (pinfunction "1_8") (pintype "passive"))
      (node (ref "X2") (pin "14") (pinfunction "1_14") (pintype "passive"))
      (node (ref "X3") (pin "14") (pinfunction "1_14") (pintype "passive"))
    )
    (net (code "23") (name "NRF24_CE") (class "Default")
      (node (ref "SV1") (pin "6") (pinfunction "6_6") (pintype "passive"))
      (node (ref "U$1") (pin "55") (pinfunction "PD8/USART3_TX(5T)_55") (pintype "bidirectional"))
    )
    (net (code "24") (name "NRF24_CS") (class "Default")
      (node (ref "SV1") (pin "5") (pinfunction "5_5") (pintype "passive"))
      (node (ref "U$1") (pin "88") (pinfunction "PD7(5T)_88") (pintype "bidirectional"))
    )
    (net (code "25") (name "NRF24_IRQ") (class "Default")
      (node (ref "SV1") (pin "1") (pinfunction "1_1") (pintype "passive"))
      (node (ref "U$1") (pin "57") (pinfunction "PD10(5T)_57") (pintype "bidirectional"))
    )
    (net (code "26") (name "NRF24_MISO") (class "Default")
      (node (ref "SV1") (pin "2") (pinfunction "2_2") (pintype "passive"))
      (node (ref "U$1") (pin "90") (pinfunction "PB4/JNTRST(5T)_90") (pintype "bidirectional"))
    )
    (net (code "27") (name "NRF24_MOSI") (class "Default")
      (node (ref "SV1") (pin "3") (pinfunction "3_3") (pintype "passive"))
      (node (ref "U$1") (pin "32") (pinfunction "PA7/ETH_MII_RX_DV/ADC12_IN7(5T)_32") (pintype "bidirectional"))
    )
    (net (code "28") (name "NRF24_SCK") (class "Default")
      (node (ref "SV1") (pin "4") (pinfunction "4_4") (pintype "passive"))
      (node (ref "U$1") (pin "30") (pinfunction "PA5/SPI1_SCK/ADC12_IN5_30") (pintype "bidirectional"))
    )
    (net (code "29") (name "NRST") (class "Default")
      (node (ref "C4") (pin "1") (pinfunction "1_1") (pintype "passive"))
      (node (ref "R7") (pin "1") (pinfunction "1_1") (pintype "passive"))
      (node (ref "S1") (pin "1") (pinfunction "1_1") (pintype "passive"))
      (node (ref "S1") (pin "2") (pinfunction "2_2") (pintype "passive"))
      (node (ref "U$1") (pin "14") (pinfunction "NRST_14") (pintype "bidirectional"))
    )
    (net (code "30") (name "Net-(D1-A)") (class "Default")
      (node (ref "C19") (pin "2") (pinfunction "2_2") (pintype "passive"))
      (node (ref "D1") (pin "2") (pinfunction "A_2") (pintype "passive"))
      (node (ref "IC1") (pin "5") (pinfunction "VO_5") (pintype "output"))
    )
    (net (code "31") (name "Net-(D3-PadA)") (class "Default")
      (node (ref "D3") (pin "A") (pinfunction "A_A") (pintype "passive"))
      (node (ref "R34") (pin "2") (pinfunction "2_2") (pintype "passive"))
    )
    (net (code "32") (name "Net-(D4-PadA)") (class "Default")
      (node (ref "D4") (pin "A") (pinfunction "A_A") (pintype "passive"))
      (node (ref "R35") (pin "2") (pinfunction "2_2") (pintype "passive"))
    )
    (net (code "33") (name "Net-(IC1-BYPASS)") (class "Default")
      (node (ref "C20") (pin "2") (pinfunction "2_2") (pintype "passive"))
      (node (ref "IC1") (pin "4") (pinfunction "BYPASS_4") (pintype "passive"))
    )
    (net (code "34") (name "Net-(SD1-CD{slash}DAT3(~{CS}))") (class "Default")
      (node (ref "R50") (pin "2") (pinfunction "2_2") (pintype "passive"))
      (node (ref "SD1") (pin "2") (pinfunction "CD/DAT3(~{CS})_2") (pintype "bidirectional"))
    )
    (net (code "35") (name "Net-(SD1-CLK(SCLK))") (class "Default")
      (node (ref "R52") (pin "2") (pinfunction "2_2") (pintype "passive"))
      (node (ref "SD1") (pin "5") (pinfunction "CLK(SCLK)_5") (pintype "input"))
    )
    (net (code "36") (name "Net-(SD1-CMD(DI))") (class "Default")
      (node (ref "R51") (pin "2") (pinfunction "2_2") (pintype "passive"))
      (node (ref "SD1") (pin "3") (pinfunction "CMD(DI)_3") (pintype "bidirectional"))
    )
    (net (code "37") (name "Net-(SD1-DAT0(DO))") (class "Default")
      (node (ref "R53") (pin "1") (pinfunction "1_1") (pintype "passive"))
      (node (ref "SD1") (pin "7") (pinfunction "DAT0(DO)_7") (pintype "bidirectional"))
    )
    (net (code "38") (name "Net-(SD1-DAT1)") (class "Default")
      (node (ref "R54") (pin "2") (pinfunction "2_2") (pintype "passive"))
      (node (ref "SD1") (pin "8") (pinfunction "DAT1_8") (pintype "bidirectional"))
    )
    (net (code "39") (name "Net-(SD1-DAT2)") (class "Default")
      (node (ref "R49") (pin "2") (pinfunction "2_2") (pintype "passive"))
      (node (ref "SD1") (pin "1") (pinfunction "DAT2_1") (pintype "bidirectional"))
    )
    (net (code "40") (name "Net-(SD1-~{CARD})") (class "Default")
      (node (ref "R55") (pin "1") (pinfunction "1_1") (pintype "passive"))
      (node (ref "SD1") (pin "9") (pinfunction "~{CARD}_9") (pintype "passive"))
    )
    (net (code "41") (name "Net-(U$1-PD5{slash}USART2_TX(5T))") (class "Default")
      (node (ref "R30") (pin "2") (pinfunction "2_2") (pintype "passive"))
      (node (ref "R32") (pin "2") (pinfunction "2_2") (pintype "passive"))
      (node (ref "U$1") (pin "86") (pinfunction "PD5/USART2_TX(5T)_86") (pintype "bidirectional"))
    )
    (net (code "42") (name "Net-(U$1-PD6{slash}USART2_RX(5T))") (class "Default")
      (node (ref "R31") (pin "2") (pinfunction "2_2") (pintype "passive"))
      (node (ref "R33") (pin "2") (pinfunction "2_2") (pintype "passive"))
      (node (ref "U$1") (pin "87") (pinfunction "PD6/USART2_RX(5T)_87") (pintype "bidirectional"))
    )
    (net (code "43") (name "Net-(U$1-PE2{slash}ETH_MII_TXD3(5T))") (class "Default")
      (node (ref "D3") (pin "C") (pinfunction "C_C") (pintype "passive"))
      (node (ref "U$1") (pin "1") (pinfunction "PE2/ETH_MII_TXD3(5T)_1") (pintype "bidirectional"))
    )
    (net (code "44") (name "Net-(U$1-PE3(5T))") (class "Default")
      (node (ref "D4") (pin "C") (pinfunction "C_C") (pintype "passive"))
      (node (ref "U$1") (pin "2") (pinfunction "PE3(5T)_2") (pintype "bidirectional"))
    )
    (net (code "45") (name "Net-(U$1-VCAP1)") (class "Default")
      (node (ref "C5") (pin "1") (pinfunction "1_1") (pintype "passive"))
      (node (ref "U$1") (pin "49") (pinfunction "VCAP1_49") (pintype "bidirectional"))
    )
    (net (code "46") (name "Net-(U$1-VCAP2)") (class "Default")
      (node (ref "C14") (pin "1") (pinfunction "1_1") (pintype "passive"))
      (node (ref "U$1") (pin "73") (pinfunction "VCAP2_73") (pintype "bidirectional"))
    )
    (net (code "47") (name "Net-(U$5-1.IN)") (class "Default")
      (node (ref "U$5") (pin "1") (pinfunction "1.IN_1") (pintype "bidirectional"))
      (node (ref "U4") (pin "VBUS1") (pinfunction "VBUS_VBUS1") (pintype "bidirectional"))
    )
    (net (code "48") (name "Net-(U$5-2.OUT)") (class "Default")
      (node (ref "R28") (pin "2") (pinfunction "2_2") (pintype "passive"))
      (node (ref "U$5") (pin "2") (pinfunction "2.OUT_2") (pintype "bidirectional"))
    )
    (net (code "49") (name "Net-(U4-D+)") (class "Default")
      (node (ref "R27") (pin "2") (pinfunction "2_2") (pintype "passive"))
      (node (ref "U4") (pin "D+1") (pinfunction "D+_D+1") (pintype "bidirectional"))
    )
    (net (code "50") (name "Net-(U4-D-)") (class "Default")
      (node (ref "R26") (pin "2") (pinfunction "2_2") (pintype "passive"))
      (node (ref "U4") (pin "D-1") (pinfunction "D-_D-1") (pintype "bidirectional"))
    )
    (net (code "51") (name "Net-(U4-USBID)") (class "Default")
      (node (ref "R29") (pin "2") (pinfunction "2_2") (pintype "passive"))
      (node (ref "U4") (pin "ID1") (pinfunction "USBID_ID1") (pintype "bidirectional"))
    )
    (net (code "52") (name "OSC32_IN") (class "Default")
      (node (ref "C3") (pin "2") (pinfunction "2_2") (pintype "passive"))
      (node (ref "U$1") (pin "8") (pinfunction "PC14/OSC32_IN(5T)_8") (pintype "bidirectional"))
      (node (ref "U$4") (pin "1") (pinfunction "1.XIN_1") (pintype "bidirectional"))
    )
    (net (code "53") (name "OSC32_OUT") (class "Default")
      (node (ref "C18") (pin "2") (pinfunction "2_2") (pintype "passive"))
      (node (ref "U$1") (pin "9") (pinfunction "PC15/OSC32_OUT(5T)_9") (pintype "bidirectional"))
      (node (ref "U$4") (pin "2") (pinfunction "2.XIN_2") (pintype "bidirectional"))
    )
    (net (code "54") (name "OSC_IN") (class "Default")
      (node (ref "C17") (pin "2") (pinfunction "2_2") (pintype "passive"))
      (node (ref "U$1") (pin "12") (pinfunction "PH0-OSC_IN(5T)_12") (pintype "bidirectional"))
      (node (ref "U$2") (pin "1") (pinfunction "1.XIN_1") (pintype "bidirectional"))
    )
    (net (code "55") (name "OSC_OUT") (class "Default")
      (node (ref "C16") (pin "2") (pinfunction "2_2") (pintype "passive"))
      (node (ref "U$1") (pin "13") (pinfunction "PH1-OSC_OUT(5T)_13") (pintype "bidirectional"))
      (node (ref "U$2") (pin "2") (pinfunction "2.XOUT_2") (pintype "bidirectional"))
    )
    (net (code "56") (name "OTG_FS_DM") (class "Default")
      (node (ref "R26") (pin "1") (pinfunction "1_1") (pintype "passive"))
      (node (ref "U$1") (pin "70") (pinfunction "PA11/USART1_CTS(5T)_70") (pintype "bidirectional"))
    )
    (net (code "57") (name "OTG_FS_DP") (class "Default")
      (node (ref "R27") (pin "1") (pinfunction "1_1") (pintype "passive"))
      (node (ref "U$1") (pin "71") (pinfunction "PA12/USART1_RTS(5T)_71") (pintype "bidirectional"))
    )
    (net (code "58") (name "OTG_FS_ID") (class "Default")
      (node (ref "R29") (pin "1") (pinfunction "1_1") (pintype "passive"))
      (node (ref "U$1") (pin "69") (pinfunction "PA10/USART1_RX(5T)_69") (pintype "bidirectional"))
    )
    (net (code "59") (name "OV_PWDN") (class "Default")
      (node (ref "R4") (pin "1") (pinfunction "1_1") (pintype "passive"))
      (node (ref "X2") (pin "17") (pinfunction "1_17") (pintype "passive"))
      (node (ref "X3") (pin "17") (pinfunction "1_17") (pintype "passive"))
    )
    (net (code "60") (name "OV_RESET") (class "Default")
      (node (ref "C25") (pin "2") (pinfunction "2_2") (pintype "passive"))
      (node (ref "R3") (pin "1") (pinfunction "1_1") (pintype "passive"))
      (node (ref "X2") (pin "19") (pinfunction "1_19") (pintype "passive"))
      (node (ref "X3") (pin "19") (pinfunction "1_19") (pintype "passive"))
    )
    (net (code "61") (name "PCLK") (class "Default")
      (node (ref "C29") (pin "2") (pinfunction "2_2") (pintype "passive"))
      (node (ref "U$1") (pin "31") (pinfunction "PA6/SPI1_MISO/ADC12_IN6(5T)_31") (pintype "bidirectional"))
      (node (ref "X2") (pin "8") (pinfunction "1_8") (pintype "passive"))
      (node (ref "X3") (pin "8") (pinfunction "1_8") (pintype "passive"))
    )
    (net (code "62") (name "SD_CD") (class "Default")
      (node (ref "R55") (pin "2") (pinfunction "2_2") (pintype "passive"))
      (node (ref "R61") (pin "1") (pinfunction "1_1") (pintype "passive"))
      (node (ref "U$1") (pin "54") (pinfunction "PB15/TIM8_CH3N(5T)_54") (pintype "bidirectional"))
    )
    (net (code "63") (name "SD_CLK") (class "Default")
      (node (ref "R52") (pin "1") (pinfunction "1_1") (pintype "passive"))
      (node (ref "U$1") (pin "80") (pinfunction "PC12/UART5_TX(5T)_80") (pintype "bidirectional"))
    )
    (net (code "64") (name "SD_CMD") (class "Default")
      (node (ref "R51") (pin "1") (pinfunction "1_1") (pintype "passive"))
      (node (ref "R58") (pin "1") (pinfunction "1_1") (pintype "passive"))
      (node (ref "U$1") (pin "83") (pinfunction "PD2/UART5_RX(5T)_83") (pintype "bidirectional"))
    )
    (net (code "65") (name "SD_DAT0") (class "Default")
      (node (ref "R53") (pin "2") (pinfunction "2_2") (pintype "passive"))
      (node (ref "R57") (pin "1") (pinfunction "1_1") (pintype "passive"))
      (node (ref "U$1") (pin "65") (pinfunction "PC8/TIM8_CH3(5T)_65") (pintype "bidirectional"))
    )
    (net (code "66") (name "SD_DAT1") (class "Default")
      (node (ref "R54") (pin "1") (pinfunction "1_1") (pintype "passive"))
      (node (ref "R56") (pin "1") (pinfunction "1_1") (pintype "passive"))
      (node (ref "U$1") (pin "66") (pinfunction "PC9/TIM3_CH4(5T)_66") (pintype "bidirectional"))
    )
    (net (code "67") (name "SD_DAT2") (class "Default")
      (node (ref "R49") (pin "1") (pinfunction "1_1") (pintype "passive"))
      (node (ref "R60") (pin "1") (pinfunction "1_1") (pintype "passive"))
      (node (ref "U$1") (pin "78") (pinfunction "PC10/UART4_TX(5T)_78") (pintype "bidirectional"))
    )
    (net (code "68") (name "SD_DAT3") (class "Default")
      (node (ref "R50") (pin "1") (pinfunction "1_1") (pintype "passive"))
      (node (ref "R59") (pin "1") (pinfunction "1_1") (pintype "passive"))
      (node (ref "U$1") (pin "79") (pinfunction "PC11/UART4_RX(5T)_79") (pintype "bidirectional"))
    )
    (net (code "69") (name "SIO_CLK") (class "Default")
      (node (ref "R10") (pin "1") (pinfunction "1_1") (pintype "passive"))
      (node (ref "U$1") (pin "95") (pinfunction "PB8/TIM10_CH1(5T)_95") (pintype "bidirectional"))
      (node (ref "X2") (pin "20") (pinfunction "1_20") (pintype "passive"))
      (node (ref "X3") (pin "20") (pinfunction "1_20") (pintype "passive"))
    )
    (net (code "70") (name "SIO_DAT") (class "Default")
      (node (ref "R11") (pin "1") (pinfunction "1_1") (pintype "passive"))
      (node (ref "U$1") (pin "96") (pinfunction "PB9/TIM11_CH1(5T)_96") (pintype "bidirectional"))
      (node (ref "X2") (pin "22") (pinfunction "1_22") (pintype "passive"))
      (node (ref "X3") (pin "22") (pinfunction "1_22") (pintype "passive"))
    )
    (net (code "71") (name "SPI2_CS") (class "Default")
      (node (ref "U$1") (pin "51") (pinfunction "PB12/ETH_MII_TXD0(5T)_51") (pintype "bidirectional"))
      (node (ref "X1") (pin "2") (pinfunction "1_2") (pintype "passive"))
    )
    (net (code "72") (name "SPI2_MISO") (class "Default")
      (node (ref "SV2") (pin "8") (pinfunction "8_8") (pintype "passive"))
      (node (ref "U$1") (pin "17") (pinfunction "PC2/ETH_MII_TXD2/ADC123_IN12(5T)_17") (pintype "bidirectional"))
      (node (ref "X1") (pin "4") (pinfunction "1_4") (pintype "passive"))
    )
    (net (code "73") (name "SPI2_MOSI") (class "Default")
      (node (ref "SV2") (pin "4") (pinfunction "4_4") (pintype "passive"))
      (node (ref "U$1") (pin "18") (pinfunction "PC3/ETH_MII_TX_CLK/ADC123_IN13(5T)_18") (pintype "bidirectional"))
      (node (ref "X1") (pin "5") (pinfunction "1_5") (pintype "passive"))
    )
    (net (code "74") (name "SPI2_SCK") (class "Default")
      (node (ref "SV2") (pin "3") (pinfunction "3_3") (pintype "passive"))
      (node (ref "U$1") (pin "52") (pinfunction "PB13/ETH_MII_TXD1(5T)_52") (pintype "bidirectional"))
      (node (ref "X1") (pin "3") (pinfunction "1_3") (pintype "passive"))
    )
    (net (code "75") (name "SWTCK") (class "Default")
      (node (ref "JP1") (pin "3") (pinfunction "3_3") (pintype "passive"))
      (node (ref "U$1") (pin "76") (pinfunction "PA14/JTCK-SWCLK(5T)_76") (pintype "bidirectional"))
    )
    (net (code "76") (name "SWTDIO") (class "Default")
      (node (ref "JP1") (pin "2") (pinfunction "2_2") (pintype "passive"))
      (node (ref "U$1") (pin "72") (pinfunction "PA13/JTMS-SWDAT(5T)_72") (pintype "bidirectional"))
    )
    (net (code "77") (name "VBUS") (class "Default")
      (node (ref "C21") (pin "2") (pinfunction "2_2") (pintype "passive"))
      (node (ref "IC1") (pin "1") (pinfunction "VIN_1") (pintype "input"))
      (node (ref "IC1") (pin "3") (pinfunction "VINH_3") (pintype "input"))
      (node (ref "R28") (pin "1") (pinfunction "1_1") (pintype "passive"))
      (node (ref "U$1") (pin "68") (pinfunction "PA9/USART1_TX(5T)_68") (pintype "bidirectional"))
    )
    (net (code "78") (name "VDDA") (class "Default")
      (node (ref "C10") (pin "2") (pinfunction "2_2") (pintype "passive"))
      (node (ref "C11") (pin "2") (pinfunction "2_2") (pintype "passive"))
      (node (ref "C12") (pin "2") (pinfunction "2_2") (pintype "passive"))
      (node (ref "C13") (pin "2") (pinfunction "2_2") (pintype "passive"))
      (node (ref "U$1") (pin "21") (pinfunction "VREF+_21") (pintype "bidirectional"))
      (node (ref "U$1") (pin "22") (pinfunction "VDDA_22") (pintype "bidirectional"))
      (node (ref "U$3") (pin "2") (pinfunction "2.OUT_2") (pintype "bidirectional"))
    )
    (net (code "79") (name "VSYNC") (class "Default")
      (node (ref "U$1") (pin "93") (pinfunction "PB7/I2C1_SDA(5T)_93") (pintype "bidirectional"))
      (node (ref "X2") (pin "18") (pinfunction "1_18") (pintype "passive"))
      (node (ref "X3") (pin "18") (pinfunction "1_18") (pintype "passive"))
    )
    (net (code "80") (name "XCLK") (class "Default")
      (node (ref "U$1") (pin "67") (pinfunction "PA8/MCO1(5T)_67") (pintype "bidirectional"))
      (node (ref "X2") (pin "12") (pinfunction "1_12") (pintype "passive"))
      (node (ref "X3") (pin "12") (pinfunction "1_12") (pintype "passive"))
    )
    (net (code "81") (name "unconnected-(U$1-PA0{slash}ETH_MII_CRS{slash}ADC123_IN0(5T)-Pad23)") (class "Default")
      (node (ref "U$1") (pin "23") (pinfunction "PA0/ETH_MII_CRS/ADC123_IN0(5T)_23") (pintype "bidirectional"))
    )
    (net (code "82") (name "unconnected-(U$1-PA1{slash}ETH_RMII_RX_CLK{slash}ADC123_IN1(5T)-Pad24)") (class "Default")
      (node (ref "U$1") (pin "24") (pinfunction "PA1/ETH_RMII_RX_CLK/ADC123_IN1(5T)_24") (pintype "bidirectional"))
    )
    (net (code "83") (name "unconnected-(U$1-PA3{slash}ETH_MII_COL{slash}ADC123_IN2(5T)-Pad26)") (class "Default")
      (node (ref "U$1") (pin "26") (pinfunction "PA3/ETH_MII_COL/ADC123_IN2(5T)_26") (pintype "bidirectional"))
    )
    (net (code "84") (name "unconnected-(U$1-PA15{slash}JTDI(5T)-Pad77)") (class "Default")
      (node (ref "U$1") (pin "77") (pinfunction "PA15/JTDI(5T)_77") (pintype "bidirectional"))
    )
    (net (code "85") (name "unconnected-(U$1-PB0{slash}ETH_MII_RXD2{slash}ADC12_IN8(5T)-Pad35)") (class "Default")
      (node (ref "U$1") (pin "35") (pinfunction "PB0/ETH_MII_RXD2/ADC12_IN8(5T)_35") (pintype "bidirectional"))
    )
    (net (code "86") (name "unconnected-(U$1-PB1{slash}ETH_MII_RXD3{slash}ADC12_IN9(5T)-Pad36)") (class "Default")
      (node (ref "U$1") (pin "36") (pinfunction "PB1/ETH_MII_RXD3/ADC12_IN9(5T)_36") (pintype "bidirectional"))
    )
    (net (code "87") (name "unconnected-(U$1-PB3{slash}JTDO(5T)-Pad89)") (class "Default")
      (node (ref "U$1") (pin "89") (pinfunction "PB3/JTDO(5T)_89") (pintype "bidirectional"))
    )
    (net (code "88") (name "unconnected-(U$1-PB5{slash}TIM3_CH2(5T)-Pad91)") (class "Default")
      (node (ref "U$1") (pin "91") (pinfunction "PB5/TIM3_CH2(5T)_91") (pintype "bidirectional"))
    )
    (net (code "89") (name "unconnected-(U$1-PB10{slash}ETH_MII_RX_ER(5T)-Pad47)") (class "Default")
      (node (ref "U$1") (pin "47") (pinfunction "PB10/ETH_MII_RX_ER(5T)_47") (pintype "bidirectional"))
    )
    (net (code "90") (name "unconnected-(U$1-PB11{slash}ETH_MII_TX_EN(5T)-Pad48)") (class "Default")
      (node (ref "U$1") (pin "48") (pinfunction "PB11/ETH_MII_TX_EN(5T)_48") (pintype "bidirectional"))
    )
    (net (code "91") (name "unconnected-(U$1-PB14{slash}TIM8_CH2N(5T)-Pad53)") (class "Default")
      (node (ref "U$1") (pin "53") (pinfunction "PB14/TIM8_CH2N(5T)_53") (pintype "bidirectional"))
    )
    (net (code "92") (name "unconnected-(U$1-PC0{slash}ADC123_IN10(5T)-Pad15)") (class "Default")
      (node (ref "U$1") (pin "15") (pinfunction "PC0/ADC123_IN10(5T)_15") (pintype "bidirectional"))
    )
    (net (code "93") (name "unconnected-(U$1-PC1{slash}ETH_MDC{slash}ADC123_IN11(5T)-Pad16)") (class "Default")
      (node (ref "U$1") (pin "16") (pinfunction "PC1/ETH_MDC/ADC123_IN11(5T)_16") (pintype "bidirectional"))
    )
    (net (code "94") (name "unconnected-(U$1-PC4{slash}ETH_MII_RXD0{slash}ADC12_IN14(5T)-Pad33)") (class "Default")
      (node (ref "U$1") (pin "33") (pinfunction "PC4/ETH_MII_RXD0/ADC12_IN14(5T)_33") (pintype "bidirectional"))
    )
    (net (code "95") (name "unconnected-(U$1-PC5{slash}ETH_MII_RXD1{slash}ADC12_IN15(5T)-Pad34)") (class "Default")
      (node (ref "U$1") (pin "34") (pinfunction "PC5/ETH_MII_RXD1/ADC12_IN15(5T)_34") (pintype "bidirectional"))
    )
    (net (code "96") (name "unconnected-(U$1-PC13(5T)-Pad7)") (class "Default")
      (node (ref "U$1") (pin "7") (pinfunction "PC13(5T)_7") (pintype "bidirectional"))
    )
    (net (code "97") (name "unconnected-(U$1-PD0{slash}CAN1_RX(5T)-Pad81)") (class "Default")
      (node (ref "U$1") (pin "81") (pinfunction "PD0/CAN1_RX(5T)_81") (pintype "bidirectional"))
    )
    (net (code "98") (name "unconnected-(U$1-PD1{slash}CAN1_TX(5T)-Pad82)") (class "Default")
      (node (ref "U$1") (pin "82") (pinfunction "PD1/CAN1_TX(5T)_82") (pintype "bidirectional"))
    )
    (net (code "99") (name "unconnected-(U$1-PD3(5T)-Pad84)") (class "Default")
      (node (ref "U$1") (pin "84") (pinfunction "PD3(5T)_84") (pintype "bidirectional"))
    )
    (net (code "100") (name "unconnected-(U$1-PD4(5T)-Pad85)") (class "Default")
      (node (ref "U$1") (pin "85") (pinfunction "PD4(5T)_85") (pintype "bidirectional"))
    )
    (net (code "101") (name "unconnected-(U$1-PD9{slash}USART3_RX(5T)-Pad56)") (class "Default")
      (node (ref "U$1") (pin "56") (pinfunction "PD9/USART3_RX(5T)_56") (pintype "bidirectional"))
    )
    (net (code "102") (name "unconnected-(U$1-PD11(5T)-Pad58)") (class "Default")
      (node (ref "U$1") (pin "58") (pinfunction "PD11(5T)_58") (pintype "bidirectional"))
    )
    (net (code "103") (name "unconnected-(U$1-PD15{slash}TIM4_CH4(5T)-Pad62)") (class "Default")
      (node (ref "U$1") (pin "62") (pinfunction "PD15/TIM4_CH4(5T)_62") (pintype "bidirectional"))
    )
    (net (code "104") (name "unconnected-(U$1-PE7{slash}TIM1_ETR(5T)-Pad38)") (class "Default")
      (node (ref "U$1") (pin "38") (pinfunction "PE7/TIM1_ETR(5T)_38") (pintype "bidirectional"))
    )
    (net (code "105") (name "unconnected-(U$1-PE8{slash}TIM1_CH1N(5T)-Pad39)") (class "Default")
      (node (ref "U$1") (pin "39") (pinfunction "PE8/TIM1_CH1N(5T)_39") (pintype "bidirectional"))
    )
    (net (code "106") (name "unconnected-(U$1-PE9{slash}TIM1_CH1(5T)-Pad40)") (class "Default")
      (node (ref "U$1") (pin "40") (pinfunction "PE9/TIM1_CH1(5T)_40") (pintype "bidirectional"))
    )
    (net (code "107") (name "unconnected-(U$1-PE10{slash}TIM1_CH2N(5T)-Pad41)") (class "Default")
      (node (ref "U$1") (pin "41") (pinfunction "PE10/TIM1_CH2N(5T)_41") (pintype "bidirectional"))
    )
    (net (code "108") (name "unconnected-(U$1-PE11{slash}TIM1_CH2(5T)-Pad42)") (class "Default")
      (node (ref "U$1") (pin "42") (pinfunction "PE11/TIM1_CH2(5T)_42") (pintype "bidirectional"))
    )
    (net (code "109") (name "unconnected-(U$1-PE12{slash}TIM1_CH3N(5T)-Pad43)") (class "Default")
      (node (ref "U$1") (pin "43") (pinfunction "PE12/TIM1_CH3N(5T)_43") (pintype "bidirectional"))
    )
    (net (code "110") (name "unconnected-(U$1-PE13{slash}TIM1_CH3(5T)-Pad44)") (class "Default")
      (node (ref "U$1") (pin "44") (pinfunction "PE13/TIM1_CH3(5T)_44") (pintype "bidirectional"))
    )
    (net (code "111") (name "unconnected-(U$1-PE14{slash}TIM1_CH4(5T)-Pad45)") (class "Default")
      (node (ref "U$1") (pin "45") (pinfunction "PE14/TIM1_CH4(5T)_45") (pintype "bidirectional"))
    )
    (net (code "112") (name "unconnected-(U$1-PE15{slash}TIM1_BKIN(5T)-Pad46)") (class "Default")
      (node (ref "U$1") (pin "46") (pinfunction "PE15/TIM1_BKIN(5T)_46") (pintype "bidirectional"))
    )
    (net (code "113") (name "unconnected-(X2C-1-Pad11)") (class "Default")
      (node (ref "X2") (pin "11") (pinfunction "1_11") (pintype "passive"))
    )
    (net (code "114") (name "unconnected-(X2E-1-Pad13)") (class "Default")
      (node (ref "X2") (pin "13") (pinfunction "1_13") (pintype "passive"))
    )
    (net (code "115") (name "unconnected-(X2Q-1-Pad24)") (class "Default")
      (node (ref "X2") (pin "24") (pinfunction "1_24") (pintype "passive"))
    )
    (net (code "116") (name "unconnected-(X3-Pad1)") (class "Default")
      (node (ref "X3") (pin "1") (pinfunction "1_1") (pintype "passive"))
    )
    (net (code "117") (name "unconnected-(X3L-1-Pad2)") (class "Default")
      (node (ref "X3") (pin "2") (pinfunction "1_2") (pintype "passive"))
    )
    (net (code "118") (name "unconnected-(X3Q-1-Pad24)") (class "Default")
      (node (ref "X3") (pin "24") (pinfunction "1_24") (pintype "passive"))
    )
  )
)
